# DL40.net
KiCad netlist of a schematic drawn in EAGLE
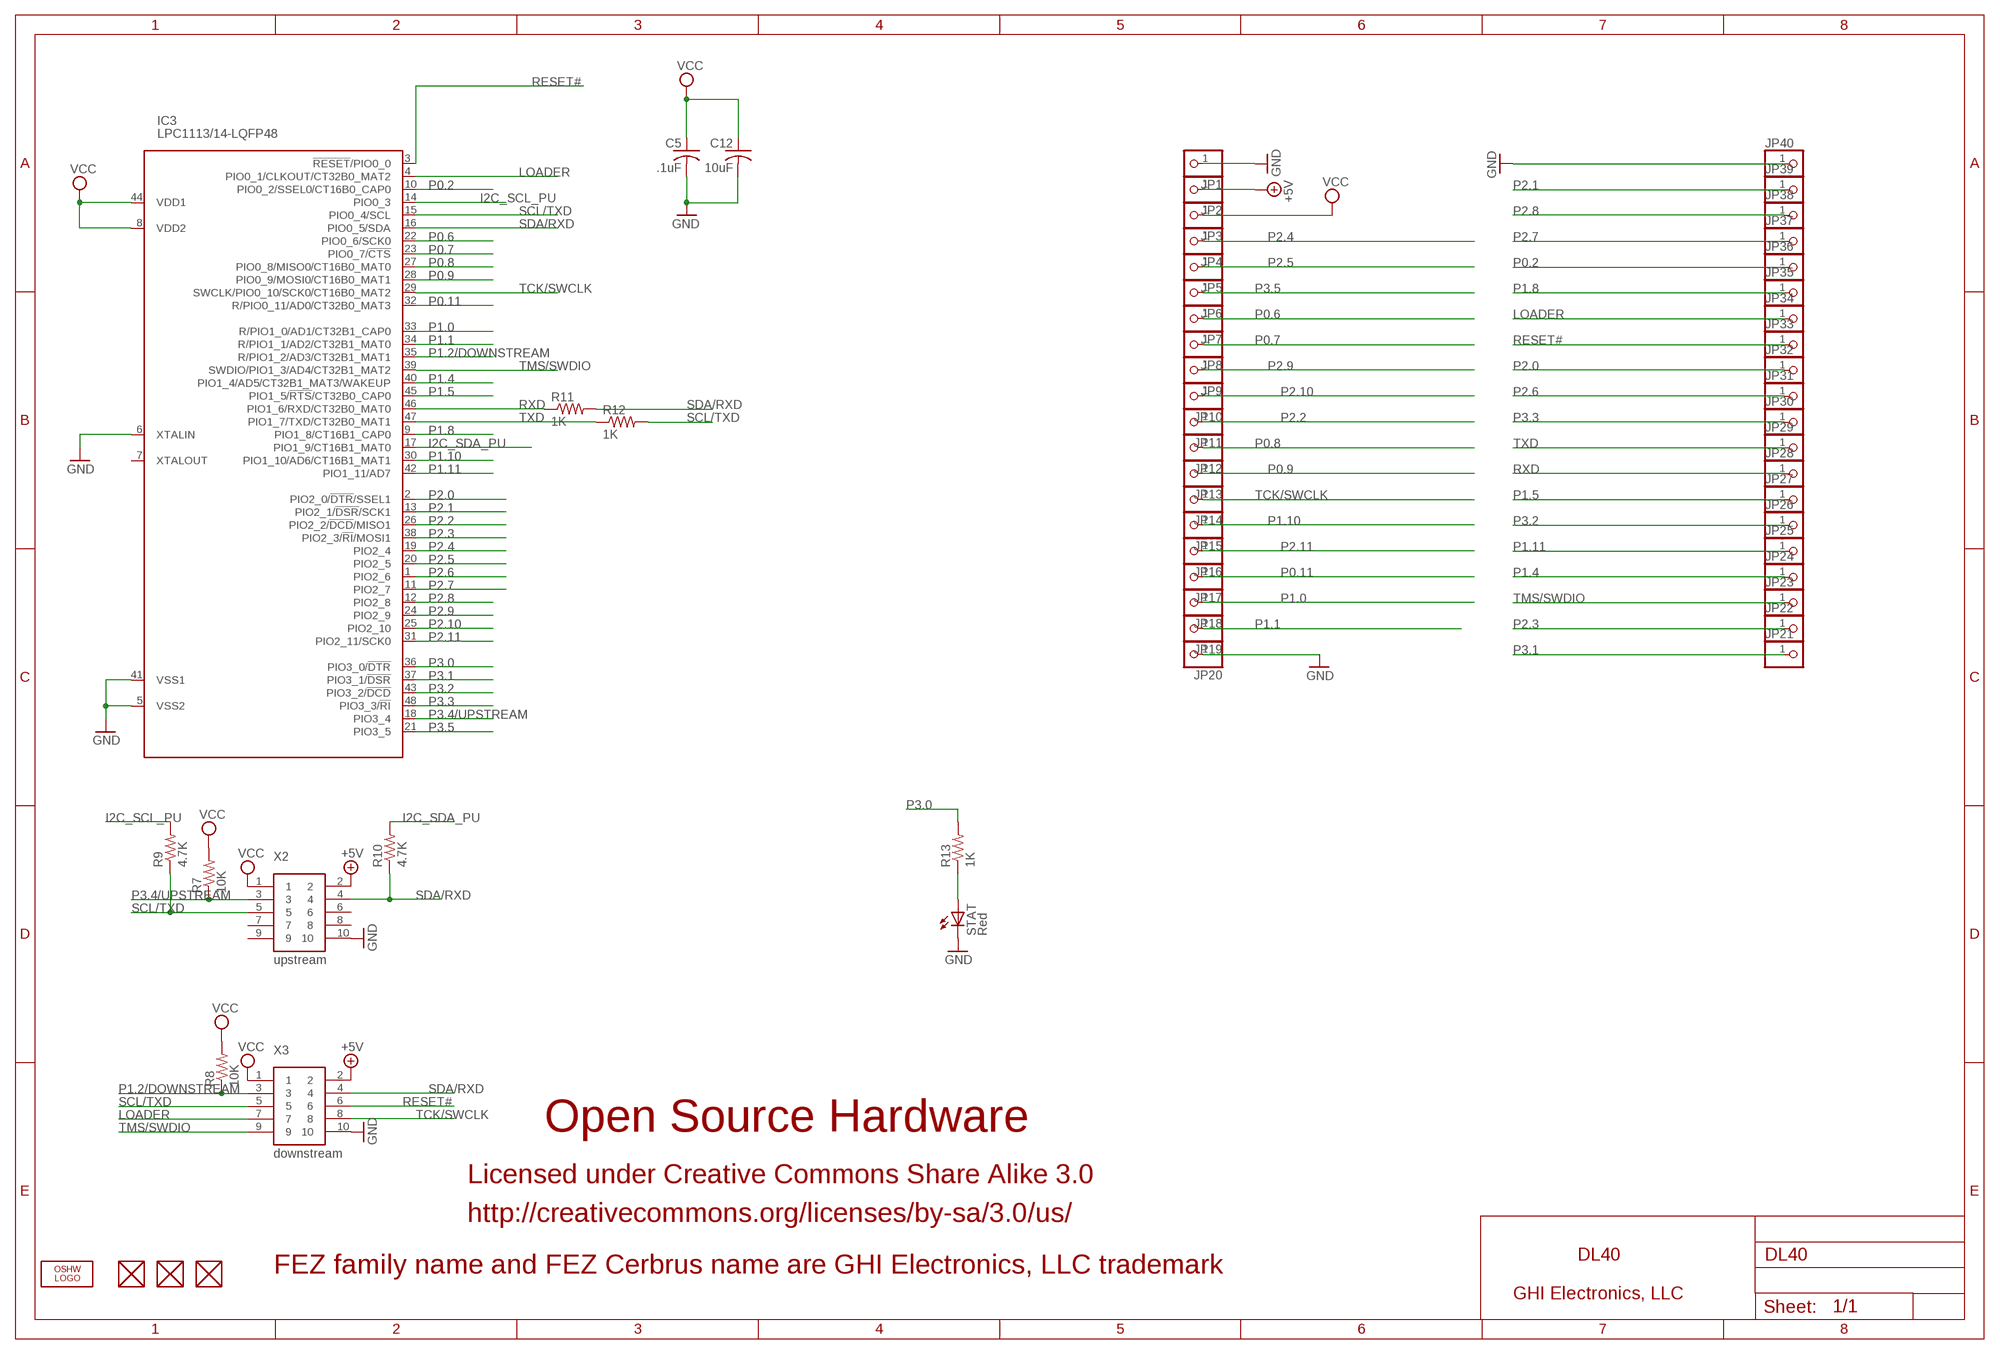
[diagram p0: schematic, sheet 1]

(export (version "E")
  (design (tool "Eeschema 10.0.6"))
  (components
    (comp (ref "C5")
      (value ".1uF")
      (footprint "eagle-import:C0603K")
      (libsource (lib "eagle-import") (part "C-USC0603K"))
    )
    (comp (ref "C12")
      (value "10uF")
      (footprint "eagle-import:C0805K")
      (libsource (lib "eagle-import") (part "C-USC0805K"))
    )
    (comp (ref "FUD4")
      (value "FIDUCIAL")
      (footprint "eagle-import:FIDUCIAL_40MIL")
      (libsource (lib "eagle-import") (part "FIDUCIAL"))
    )
    (comp (ref "FUD5")
      (value "FIDUCIAL")
      (footprint "eagle-import:FIDUCIAL_40MIL")
      (libsource (lib "eagle-import") (part "FIDUCIAL"))
    )
    (comp (ref "FUD6")
      (value "FIDUCIAL")
      (footprint "eagle-import:FIDUCIAL_40MIL")
      (libsource (lib "eagle-import") (part "FIDUCIAL"))
    )
    (comp (ref "IC3")
      (value "LPC1113/14-LQFP48")
      (footprint "eagle-import:LQFP48")
      (libsource (lib "eagle-import") (part "LPC1113/14-LQFP48"))
    )
    (comp (ref "JP1")
      (value "PINHD-1X1")
      (footprint "eagle-import:1X01")
      (libsource (lib "eagle-import") (part "PINHD-1X1"))
    )
    (comp (ref "JP2")
      (value "PINHD-1X1")
      (footprint "eagle-import:1X01")
      (libsource (lib "eagle-import") (part "PINHD-1X1"))
    )
    (comp (ref "JP3")
      (value "PINHD-1X1")
      (footprint "eagle-import:1X01")
      (libsource (lib "eagle-import") (part "PINHD-1X1"))
    )
    (comp (ref "JP4")
      (value "PINHD-1X1")
      (footprint "eagle-import:1X01")
      (libsource (lib "eagle-import") (part "PINHD-1X1"))
    )
    (comp (ref "JP5")
      (value "PINHD-1X1")
      (footprint "eagle-import:1X01")
      (libsource (lib "eagle-import") (part "PINHD-1X1"))
    )
    (comp (ref "JP6")
      (value "PINHD-1X1")
      (footprint "eagle-import:1X01")
      (libsource (lib "eagle-import") (part "PINHD-1X1"))
    )
    (comp (ref "JP7")
      (value "PINHD-1X1")
      (footprint "eagle-import:1X01")
      (libsource (lib "eagle-import") (part "PINHD-1X1"))
    )
    (comp (ref "JP8")
      (value "PINHD-1X1")
      (footprint "eagle-import:1X01")
      (libsource (lib "eagle-import") (part "PINHD-1X1"))
    )
    (comp (ref "JP9")
      (value "PINHD-1X1")
      (footprint "eagle-import:1X01")
      (libsource (lib "eagle-import") (part "PINHD-1X1"))
    )
    (comp (ref "JP10")
      (value "PINHD-1X1")
      (footprint "eagle-import:1X01")
      (libsource (lib "eagle-import") (part "PINHD-1X1"))
    )
    (comp (ref "JP11")
      (value "PINHD-1X1")
      (footprint "eagle-import:1X01")
      (libsource (lib "eagle-import") (part "PINHD-1X1"))
    )
    (comp (ref "JP12")
      (value "PINHD-1X1")
      (footprint "eagle-import:1X01")
      (libsource (lib "eagle-import") (part "PINHD-1X1"))
    )
    (comp (ref "JP13")
      (value "PINHD-1X1")
      (footprint "eagle-import:1X01")
      (libsource (lib "eagle-import") (part "PINHD-1X1"))
    )
    (comp (ref "JP14")
      (value "PINHD-1X1")
      (footprint "eagle-import:1X01")
      (libsource (lib "eagle-import") (part "PINHD-1X1"))
    )
    (comp (ref "JP15")
      (value "PINHD-1X1")
      (footprint "eagle-import:1X01")
      (libsource (lib "eagle-import") (part "PINHD-1X1"))
    )
    (comp (ref "JP16")
      (value "PINHD-1X1")
      (footprint "eagle-import:1X01")
      (libsource (lib "eagle-import") (part "PINHD-1X1"))
    )
    (comp (ref "JP17")
      (value "PINHD-1X1")
      (footprint "eagle-import:1X01")
      (libsource (lib "eagle-import") (part "PINHD-1X1"))
    )
    (comp (ref "JP18")
      (value "PINHD-1X1")
      (footprint "eagle-import:1X01")
      (libsource (lib "eagle-import") (part "PINHD-1X1"))
    )
    (comp (ref "JP19")
      (value "PINHD-1X1")
      (footprint "eagle-import:1X01")
      (libsource (lib "eagle-import") (part "PINHD-1X1"))
    )
    (comp (ref "JP20")
      (value "PINHD-1X1")
      (footprint "eagle-import:1X01")
      (libsource (lib "eagle-import") (part "PINHD-1X1"))
    )
    (comp (ref "JP21")
      (value "PINHD-1X1")
      (footprint "eagle-import:1X01")
      (libsource (lib "eagle-import") (part "PINHD-1X1"))
    )
    (comp (ref "JP22")
      (value "PINHD-1X1")
      (footprint "eagle-import:1X01")
      (libsource (lib "eagle-import") (part "PINHD-1X1"))
    )
    (comp (ref "JP23")
      (value "PINHD-1X1")
      (footprint "eagle-import:1X01")
      (libsource (lib "eagle-import") (part "PINHD-1X1"))
    )
    (comp (ref "JP24")
      (value "PINHD-1X1")
      (footprint "eagle-import:1X01")
      (libsource (lib "eagle-import") (part "PINHD-1X1"))
    )
    (comp (ref "JP25")
      (value "PINHD-1X1")
      (footprint "eagle-import:1X01")
      (libsource (lib "eagle-import") (part "PINHD-1X1"))
    )
    (comp (ref "JP26")
      (value "PINHD-1X1")
      (footprint "eagle-import:1X01")
      (libsource (lib "eagle-import") (part "PINHD-1X1"))
    )
    (comp (ref "JP27")
      (value "PINHD-1X1")
      (footprint "eagle-import:1X01")
      (libsource (lib "eagle-import") (part "PINHD-1X1"))
    )
    (comp (ref "JP28")
      (value "PINHD-1X1")
      (footprint "eagle-import:1X01")
      (libsource (lib "eagle-import") (part "PINHD-1X1"))
    )
    (comp (ref "JP29")
      (value "PINHD-1X1")
      (footprint "eagle-import:1X01")
      (libsource (lib "eagle-import") (part "PINHD-1X1"))
    )
    (comp (ref "JP30")
      (value "PINHD-1X1")
      (footprint "eagle-import:1X01")
      (libsource (lib "eagle-import") (part "PINHD-1X1"))
    )
    (comp (ref "JP31")
      (value "PINHD-1X1")
      (footprint "eagle-import:1X01")
      (libsource (lib "eagle-import") (part "PINHD-1X1"))
    )
    (comp (ref "JP32")
      (value "PINHD-1X1")
      (footprint "eagle-import:1X01")
      (libsource (lib "eagle-import") (part "PINHD-1X1"))
    )
    (comp (ref "JP33")
      (value "PINHD-1X1")
      (footprint "eagle-import:1X01")
      (libsource (lib "eagle-import") (part "PINHD-1X1"))
    )
    (comp (ref "JP34")
      (value "PINHD-1X1")
      (footprint "eagle-import:1X01")
      (libsource (lib "eagle-import") (part "PINHD-1X1"))
    )
    (comp (ref "JP35")
      (value "PINHD-1X1")
      (footprint "eagle-import:1X01")
      (libsource (lib "eagle-import") (part "PINHD-1X1"))
    )
    (comp (ref "JP36")
      (value "PINHD-1X1")
      (footprint "eagle-import:1X01")
      (libsource (lib "eagle-import") (part "PINHD-1X1"))
    )
    (comp (ref "JP37")
      (value "PINHD-1X1")
      (footprint "eagle-import:1X01")
      (libsource (lib "eagle-import") (part "PINHD-1X1"))
    )
    (comp (ref "JP38")
      (value "PINHD-1X1")
      (footprint "eagle-import:1X01")
      (libsource (lib "eagle-import") (part "PINHD-1X1"))
    )
    (comp (ref "JP39")
      (value "PINHD-1X1")
      (footprint "eagle-import:1X01")
      (libsource (lib "eagle-import") (part "PINHD-1X1"))
    )
    (comp (ref "JP40")
      (value "PINHD-1X1")
      (footprint "eagle-import:1X01")
      (libsource (lib "eagle-import") (part "PINHD-1X1"))
    )
    (comp (ref "LOGO2")
      (value "LOGO-OSHW-FILLX0200-NT")
      (footprint "eagle-import:OSHW_FILLX200_NOTEXT")
      (libsource (lib "eagle-import") (part "LOGO-OSHW-FILLX0200-NT"))
    )
    (comp (ref "R7")
      (value "10K")
      (footprint "eagle-import:R0603")
      (libsource (lib "eagle-import") (part "R-US_R0603"))
    )
    (comp (ref "R8")
      (value "10K")
      (footprint "eagle-import:R0603")
      (libsource (lib "eagle-import") (part "R-US_R0603"))
    )
    (comp (ref "R9")
      (value "4.7K")
      (footprint "eagle-import:R0603")
      (libsource (lib "eagle-import") (part "R-US_R0603"))
    )
    (comp (ref "R10")
      (value "4.7K")
      (footprint "eagle-import:R0603")
      (libsource (lib "eagle-import") (part "R-US_R0603"))
    )
    (comp (ref "R11")
      (value "1K")
      (footprint "eagle-import:R0603")
      (libsource (lib "eagle-import") (part "R-US_R0603"))
    )
    (comp (ref "R12")
      (value "1K")
      (footprint "eagle-import:R0603")
      (libsource (lib "eagle-import") (part "R-US_R0603"))
    )
    (comp (ref "R13")
      (value "1K")
      (footprint "eagle-import:R0603")
      (libsource (lib "eagle-import") (part "R-US_R0603"))
    )
    (comp (ref "STAT")
      (value "Red")
      (footprint "eagle-import:CHIPLED_0805")
      (libsource (lib "eagle-import") (part "LEDCHIPLED_0805"))
    )
    (comp (ref "X2")
      (value "upstream")
      (footprint "eagle-import:2X5_1.27MM")
      (libsource (lib "eagle-import") (part "2X5_1.27MM"))
    )
    (comp (ref "X3")
      (value "downstream")
      (footprint "eagle-import:2X5_1.27MM")
      (libsource (lib "eagle-import") (part "2X5_1.27MM"))
    )
  )
  (nets
    (net (code "1") (name "+5V") (class "Default")
      (node (ref "JP2") (pin "1") (pinfunction "1_1") (pintype "passive"))
      (node (ref "X2") (pin "2") (pinfunction "2_2") (pintype "bidirectional"))
      (node (ref "X3") (pin "2") (pinfunction "2_2") (pintype "bidirectional"))
    )
    (net (code "2") (name "/I2C_SCL_PU") (class "Default")
      (node (ref "IC3") (pin "14") (pinfunction "PIO0_3_14") (pintype "bidirectional"))
      (node (ref "R9") (pin "2") (pinfunction "2_2") (pintype "passive"))
    )
    (net (code "3") (name "/I2C_SDA_PU") (class "Default")
      (node (ref "IC3") (pin "17") (pinfunction "PIO1_9/CT16B1_MAT0_17") (pintype "bidirectional"))
      (node (ref "R10") (pin "2") (pinfunction "2_2") (pintype "passive"))
    )
    (net (code "4") (name "/LOADER") (class "Default")
      (node (ref "IC3") (pin "4") (pinfunction "PIO0_1/CLKOUT/CT32B0_MAT2_4") (pintype "bidirectional"))
      (node (ref "JP34") (pin "1") (pinfunction "1_1") (pintype "passive"))
      (node (ref "X3") (pin "7") (pinfunction "7_7") (pintype "bidirectional"))
    )
    (net (code "5") (name "/P0.2") (class "Default")
      (node (ref "IC3") (pin "10") (pinfunction "PIO0_2/SSEL0/CT16B0_CAP0_10") (pintype "bidirectional"))
      (node (ref "JP36") (pin "1") (pinfunction "1_1") (pintype "passive"))
    )
    (net (code "6") (name "/P0.6") (class "Default")
      (node (ref "IC3") (pin "22") (pinfunction "PIO0_6/SCK0_22") (pintype "bidirectional"))
      (node (ref "JP7") (pin "1") (pinfunction "1_1") (pintype "passive"))
    )
    (net (code "7") (name "/P0.7") (class "Default")
      (node (ref "IC3") (pin "23") (pinfunction "PIO0_7/~{CTS}_23") (pintype "bidirectional"))
      (node (ref "JP8") (pin "1") (pinfunction "1_1") (pintype "passive"))
    )
    (net (code "8") (name "/P0.8") (class "Default")
      (node (ref "IC3") (pin "27") (pinfunction "PIO0_8/MISO0/CT16B0_MAT0_27") (pintype "bidirectional"))
      (node (ref "JP12") (pin "1") (pinfunction "1_1") (pintype "passive"))
    )
    (net (code "9") (name "/P0.9") (class "Default")
      (node (ref "IC3") (pin "28") (pinfunction "PIO0_9/MOSI0/CT16B0_MAT1_28") (pintype "bidirectional"))
      (node (ref "JP13") (pin "1") (pinfunction "1_1") (pintype "passive"))
    )
    (net (code "10") (name "/P0.11") (class "Default")
      (node (ref "IC3") (pin "32") (pinfunction "R/PIO0_11/AD0/CT32B0_MAT3_32") (pintype "bidirectional"))
      (node (ref "JP17") (pin "1") (pinfunction "1_1") (pintype "passive"))
    )
    (net (code "11") (name "/P1.0") (class "Default")
      (node (ref "IC3") (pin "33") (pinfunction "R/PIO1_0/AD1/CT32B1_CAP0_33") (pintype "bidirectional"))
      (node (ref "JP18") (pin "1") (pinfunction "1_1") (pintype "passive"))
    )
    (net (code "12") (name "/P1.1") (class "Default")
      (node (ref "IC3") (pin "34") (pinfunction "R/PIO1_1/AD2/CT32B1_MAT0_34") (pintype "bidirectional"))
      (node (ref "JP19") (pin "1") (pinfunction "1_1") (pintype "passive"))
    )
    (net (code "13") (name "/P1.2{slash}DOWNSTREAM") (class "Default")
      (node (ref "IC3") (pin "35") (pinfunction "R/PIO1_2/AD3/CT32B1_MAT1_35") (pintype "bidirectional"))
      (node (ref "R8") (pin "1") (pinfunction "1_1") (pintype "passive"))
      (node (ref "X3") (pin "3") (pinfunction "3_3") (pintype "bidirectional"))
    )
    (net (code "14") (name "/P1.4") (class "Default")
      (node (ref "IC3") (pin "40") (pinfunction "PIO1_4/AD5/CT32B1_MAT3/WAKEUP_40") (pintype "bidirectional"))
      (node (ref "JP24") (pin "1") (pinfunction "1_1") (pintype "passive"))
    )
    (net (code "15") (name "/P1.5") (class "Default")
      (node (ref "IC3") (pin "45") (pinfunction "PIO1_5/~{RTS}/CT32B0_CAP0_45") (pintype "bidirectional"))
      (node (ref "JP27") (pin "1") (pinfunction "1_1") (pintype "passive"))
    )
    (net (code "16") (name "/P1.8") (class "Default")
      (node (ref "IC3") (pin "9") (pinfunction "PIO1_8/CT16B1_CAP0_9") (pintype "bidirectional"))
      (node (ref "JP35") (pin "1") (pinfunction "1_1") (pintype "passive"))
    )
    (net (code "17") (name "/P1.10") (class "Default")
      (node (ref "IC3") (pin "30") (pinfunction "PIO1_10/AD6/CT16B1_MAT1_30") (pintype "bidirectional"))
      (node (ref "JP15") (pin "1") (pinfunction "1_1") (pintype "passive"))
    )
    (net (code "18") (name "/P1.11") (class "Default")
      (node (ref "IC3") (pin "42") (pinfunction "PIO1_11/AD7_42") (pintype "bidirectional"))
      (node (ref "JP25") (pin "1") (pinfunction "1_1") (pintype "passive"))
    )
    (net (code "19") (name "/P2.0") (class "Default")
      (node (ref "IC3") (pin "2") (pinfunction "PIO2_0/~{DTR}/SSEL1_2") (pintype "bidirectional"))
      (node (ref "JP32") (pin "1") (pinfunction "1_1") (pintype "passive"))
    )
    (net (code "20") (name "/P2.1") (class "Default")
      (node (ref "IC3") (pin "13") (pinfunction "PIO2_1/~{DSR}/SCK1_13") (pintype "bidirectional"))
      (node (ref "JP39") (pin "1") (pinfunction "1_1") (pintype "passive"))
    )
    (net (code "21") (name "/P2.2") (class "Default")
      (node (ref "IC3") (pin "26") (pinfunction "PIO2_2/~{DCD}/MISO1_26") (pintype "bidirectional"))
      (node (ref "JP11") (pin "1") (pinfunction "1_1") (pintype "passive"))
    )
    (net (code "22") (name "/P2.3") (class "Default")
      (node (ref "IC3") (pin "38") (pinfunction "PIO2_3/~{RI}/MOSI1_38") (pintype "bidirectional"))
      (node (ref "JP22") (pin "1") (pinfunction "1_1") (pintype "passive"))
    )
    (net (code "23") (name "/P2.4") (class "Default")
      (node (ref "IC3") (pin "19") (pinfunction "PIO2_4_19") (pintype "bidirectional"))
      (node (ref "JP4") (pin "1") (pinfunction "1_1") (pintype "passive"))
    )
    (net (code "24") (name "/P2.5") (class "Default")
      (node (ref "IC3") (pin "20") (pinfunction "PIO2_5_20") (pintype "bidirectional"))
      (node (ref "JP5") (pin "1") (pinfunction "1_1") (pintype "passive"))
    )
    (net (code "25") (name "/P2.6") (class "Default")
      (node (ref "IC3") (pin "1") (pinfunction "PIO2_6_1") (pintype "bidirectional"))
      (node (ref "JP31") (pin "1") (pinfunction "1_1") (pintype "passive"))
    )
    (net (code "26") (name "/P2.7") (class "Default")
      (node (ref "IC3") (pin "11") (pinfunction "PIO2_7_11") (pintype "bidirectional"))
      (node (ref "JP37") (pin "1") (pinfunction "1_1") (pintype "passive"))
    )
    (net (code "27") (name "/P2.8") (class "Default")
      (node (ref "IC3") (pin "12") (pinfunction "PIO2_8_12") (pintype "bidirectional"))
      (node (ref "JP38") (pin "1") (pinfunction "1_1") (pintype "passive"))
    )
    (net (code "28") (name "/P2.9") (class "Default")
      (node (ref "IC3") (pin "24") (pinfunction "PIO2_9_24") (pintype "bidirectional"))
      (node (ref "JP9") (pin "1") (pinfunction "1_1") (pintype "passive"))
    )
    (net (code "29") (name "/P2.10") (class "Default")
      (node (ref "IC3") (pin "25") (pinfunction "PIO2_10_25") (pintype "bidirectional"))
      (node (ref "JP10") (pin "1") (pinfunction "1_1") (pintype "passive"))
    )
    (net (code "30") (name "/P2.11") (class "Default")
      (node (ref "IC3") (pin "31") (pinfunction "PIO2_11/SCK0_31") (pintype "bidirectional"))
      (node (ref "JP16") (pin "1") (pinfunction "1_1") (pintype "passive"))
    )
    (net (code "31") (name "/P3.0") (class "Default")
      (node (ref "IC3") (pin "36") (pinfunction "PIO3_0/~{DTR}_36") (pintype "bidirectional"))
      (node (ref "R13") (pin "2") (pinfunction "2_2") (pintype "passive"))
    )
    (net (code "32") (name "/P3.1") (class "Default")
      (node (ref "IC3") (pin "37") (pinfunction "PIO3_1/~{DSR}_37") (pintype "bidirectional"))
      (node (ref "JP21") (pin "1") (pinfunction "1_1") (pintype "passive"))
    )
    (net (code "33") (name "/P3.2") (class "Default")
      (node (ref "IC3") (pin "43") (pinfunction "PIO3_2/~{DCD}_43") (pintype "bidirectional"))
      (node (ref "JP26") (pin "1") (pinfunction "1_1") (pintype "passive"))
    )
    (net (code "34") (name "/P3.3") (class "Default")
      (node (ref "IC3") (pin "48") (pinfunction "PIO3_3/~{RI}_48") (pintype "bidirectional"))
      (node (ref "JP30") (pin "1") (pinfunction "1_1") (pintype "passive"))
    )
    (net (code "35") (name "/P3.4{slash}UPSTREAM") (class "Default")
      (node (ref "IC3") (pin "18") (pinfunction "PIO3_4_18") (pintype "bidirectional"))
      (node (ref "R7") (pin "1") (pinfunction "1_1") (pintype "passive"))
      (node (ref "X2") (pin "3") (pinfunction "3_3") (pintype "bidirectional"))
    )
    (net (code "36") (name "/P3.5") (class "Default")
      (node (ref "IC3") (pin "21") (pinfunction "PIO3_5_21") (pintype "bidirectional"))
      (node (ref "JP6") (pin "1") (pinfunction "1_1") (pintype "passive"))
    )
    (net (code "37") (name "/RESET#") (class "Default")
      (node (ref "IC3") (pin "3") (pinfunction "~{RESET}/PIO0_0_3") (pintype "bidirectional"))
      (node (ref "JP33") (pin "1") (pinfunction "1_1") (pintype "passive"))
      (node (ref "X3") (pin "6") (pinfunction "6_6") (pintype "bidirectional"))
    )
    (net (code "38") (name "/RXD") (class "Default")
      (node (ref "IC3") (pin "46") (pinfunction "PIO1_6/RXD/CT32B0_MAT0_46") (pintype "bidirectional"))
      (node (ref "JP28") (pin "1") (pinfunction "1_1") (pintype "passive"))
      (node (ref "R11") (pin "1") (pinfunction "1_1") (pintype "passive"))
    )
    (net (code "39") (name "/SCL{slash}TXD") (class "Default")
      (node (ref "IC3") (pin "15") (pinfunction "PIO0_4/SCL_15") (pintype "bidirectional"))
      (node (ref "R12") (pin "2") (pinfunction "2_2") (pintype "passive"))
      (node (ref "R9") (pin "1") (pinfunction "1_1") (pintype "passive"))
      (node (ref "X2") (pin "5") (pinfunction "5_5") (pintype "bidirectional"))
      (node (ref "X3") (pin "5") (pinfunction "5_5") (pintype "bidirectional"))
    )
    (net (code "40") (name "/SDA{slash}RXD") (class "Default")
      (node (ref "IC3") (pin "16") (pinfunction "PIO0_5/SDA_16") (pintype "bidirectional"))
      (node (ref "R10") (pin "1") (pinfunction "1_1") (pintype "passive"))
      (node (ref "R11") (pin "2") (pinfunction "2_2") (pintype "passive"))
      (node (ref "X2") (pin "4") (pinfunction "4_4") (pintype "bidirectional"))
      (node (ref "X3") (pin "4") (pinfunction "4_4") (pintype "bidirectional"))
    )
    (net (code "41") (name "/TCK{slash}SWCLK") (class "Default")
      (node (ref "IC3") (pin "29") (pinfunction "SWCLK/PIO0_10/SCK0/CT16B0_MAT2_29") (pintype "bidirectional"))
      (node (ref "JP14") (pin "1") (pinfunction "1_1") (pintype "passive"))
      (node (ref "X3") (pin "8") (pinfunction "8_8") (pintype "bidirectional"))
    )
    (net (code "42") (name "/TMS{slash}SWDIO") (class "Default")
      (node (ref "IC3") (pin "39") (pinfunction "SWDIO/PIO1_3/AD4/CT32B1_MAT2_39") (pintype "bidirectional"))
      (node (ref "JP23") (pin "1") (pinfunction "1_1") (pintype "passive"))
      (node (ref "X3") (pin "9") (pinfunction "9_9") (pintype "bidirectional"))
    )
    (net (code "43") (name "/TXD") (class "Default")
      (node (ref "IC3") (pin "47") (pinfunction "PIO1_7/TXD/CT32B0_MAT1_47") (pintype "bidirectional"))
      (node (ref "JP29") (pin "1") (pinfunction "1_1") (pintype "passive"))
      (node (ref "R12") (pin "1") (pinfunction "1_1") (pintype "passive"))
    )
    (net (code "44") (name "GND") (class "Default")
      (node (ref "C12") (pin "2") (pinfunction "2_2") (pintype "passive"))
      (node (ref "C5") (pin "2") (pinfunction "2_2") (pintype "passive"))
      (node (ref "IC3") (pin "41") (pinfunction "VSS1_41") (pintype "power_in"))
      (node (ref "IC3") (pin "5") (pinfunction "VSS2_5") (pintype "power_in"))
      (node (ref "IC3") (pin "6") (pinfunction "XTALIN_6") (pintype "passive"))
      (node (ref "JP1") (pin "1") (pinfunction "1_1") (pintype "passive"))
      (node (ref "JP20") (pin "1") (pinfunction "1_1") (pintype "passive"))
      (node (ref "JP40") (pin "1") (pinfunction "1_1") (pintype "passive"))
      (node (ref "STAT") (pin "C") (pinfunction "C_C") (pintype "passive"))
      (node (ref "X2") (pin "10") (pinfunction "10_10") (pintype "bidirectional"))
      (node (ref "X3") (pin "10") (pinfunction "10_10") (pintype "bidirectional"))
    )
    (net (code "45") (name "Net-(R13-Pad1)") (class "Default")
      (node (ref "R13") (pin "1") (pinfunction "1_1") (pintype "passive"))
      (node (ref "STAT") (pin "A") (pinfunction "A_A") (pintype "passive"))
    )
    (net (code "46") (name "VCC") (class "Default")
      (node (ref "C12") (pin "1") (pinfunction "1_1") (pintype "passive"))
      (node (ref "C5") (pin "1") (pinfunction "1_1") (pintype "passive"))
      (node (ref "IC3") (pin "44") (pinfunction "VDD1_44") (pintype "power_in"))
      (node (ref "IC3") (pin "8") (pinfunction "VDD2_8") (pintype "power_in"))
      (node (ref "JP3") (pin "1") (pinfunction "1_1") (pintype "passive"))
      (node (ref "R7") (pin "2") (pinfunction "2_2") (pintype "passive"))
      (node (ref "R8") (pin "2") (pinfunction "2_2") (pintype "passive"))
      (node (ref "X2") (pin "1") (pinfunction "1_1") (pintype "bidirectional"))
      (node (ref "X3") (pin "1") (pinfunction "1_1") (pintype "bidirectional"))
    )
    (net (code "47") (name "unconnected-(FUD4-PadP$1)") (class "Default")
      (node (ref "FUD4") (pin "P$1") (pinfunction "P$1_P$1") (pintype "no_connect"))
    )
    (net (code "48") (name "unconnected-(FUD5-PadP$1)") (class "Default")
      (node (ref "FUD5") (pin "P$1") (pinfunction "P$1_P$1") (pintype "no_connect"))
    )
    (net (code "49") (name "unconnected-(FUD6-PadP$1)") (class "Default")
      (node (ref "FUD6") (pin "P$1") (pinfunction "P$1_P$1") (pintype "no_connect"))
    )
    (net (code "50") (name "unconnected-(IC3-XTALOUT-Pad7)") (class "Default")
      (node (ref "IC3") (pin "7") (pinfunction "XTALOUT_7") (pintype "passive"))
    )
    (net (code "51") (name "unconnected-(X2-Pad6)") (class "Default")
      (node (ref "X2") (pin "6") (pinfunction "6_6") (pintype "bidirectional"))
    )
    (net (code "52") (name "unconnected-(X2-Pad7)") (class "Default")
      (node (ref "X2") (pin "7") (pinfunction "7_7") (pintype "bidirectional"))
    )
    (net (code "53") (name "unconnected-(X2-Pad8)") (class "Default")
      (node (ref "X2") (pin "8") (pinfunction "8_8") (pintype "bidirectional"))
    )
    (net (code "54") (name "unconnected-(X2-Pad9)") (class "Default")
      (node (ref "X2") (pin "9") (pinfunction "9_9") (pintype "bidirectional"))
    )
  )
)
